# AetherMesh_Test_Fixture_Mezz_V1_0.net
KiCad netlist of a schematic drawn in EAGLE
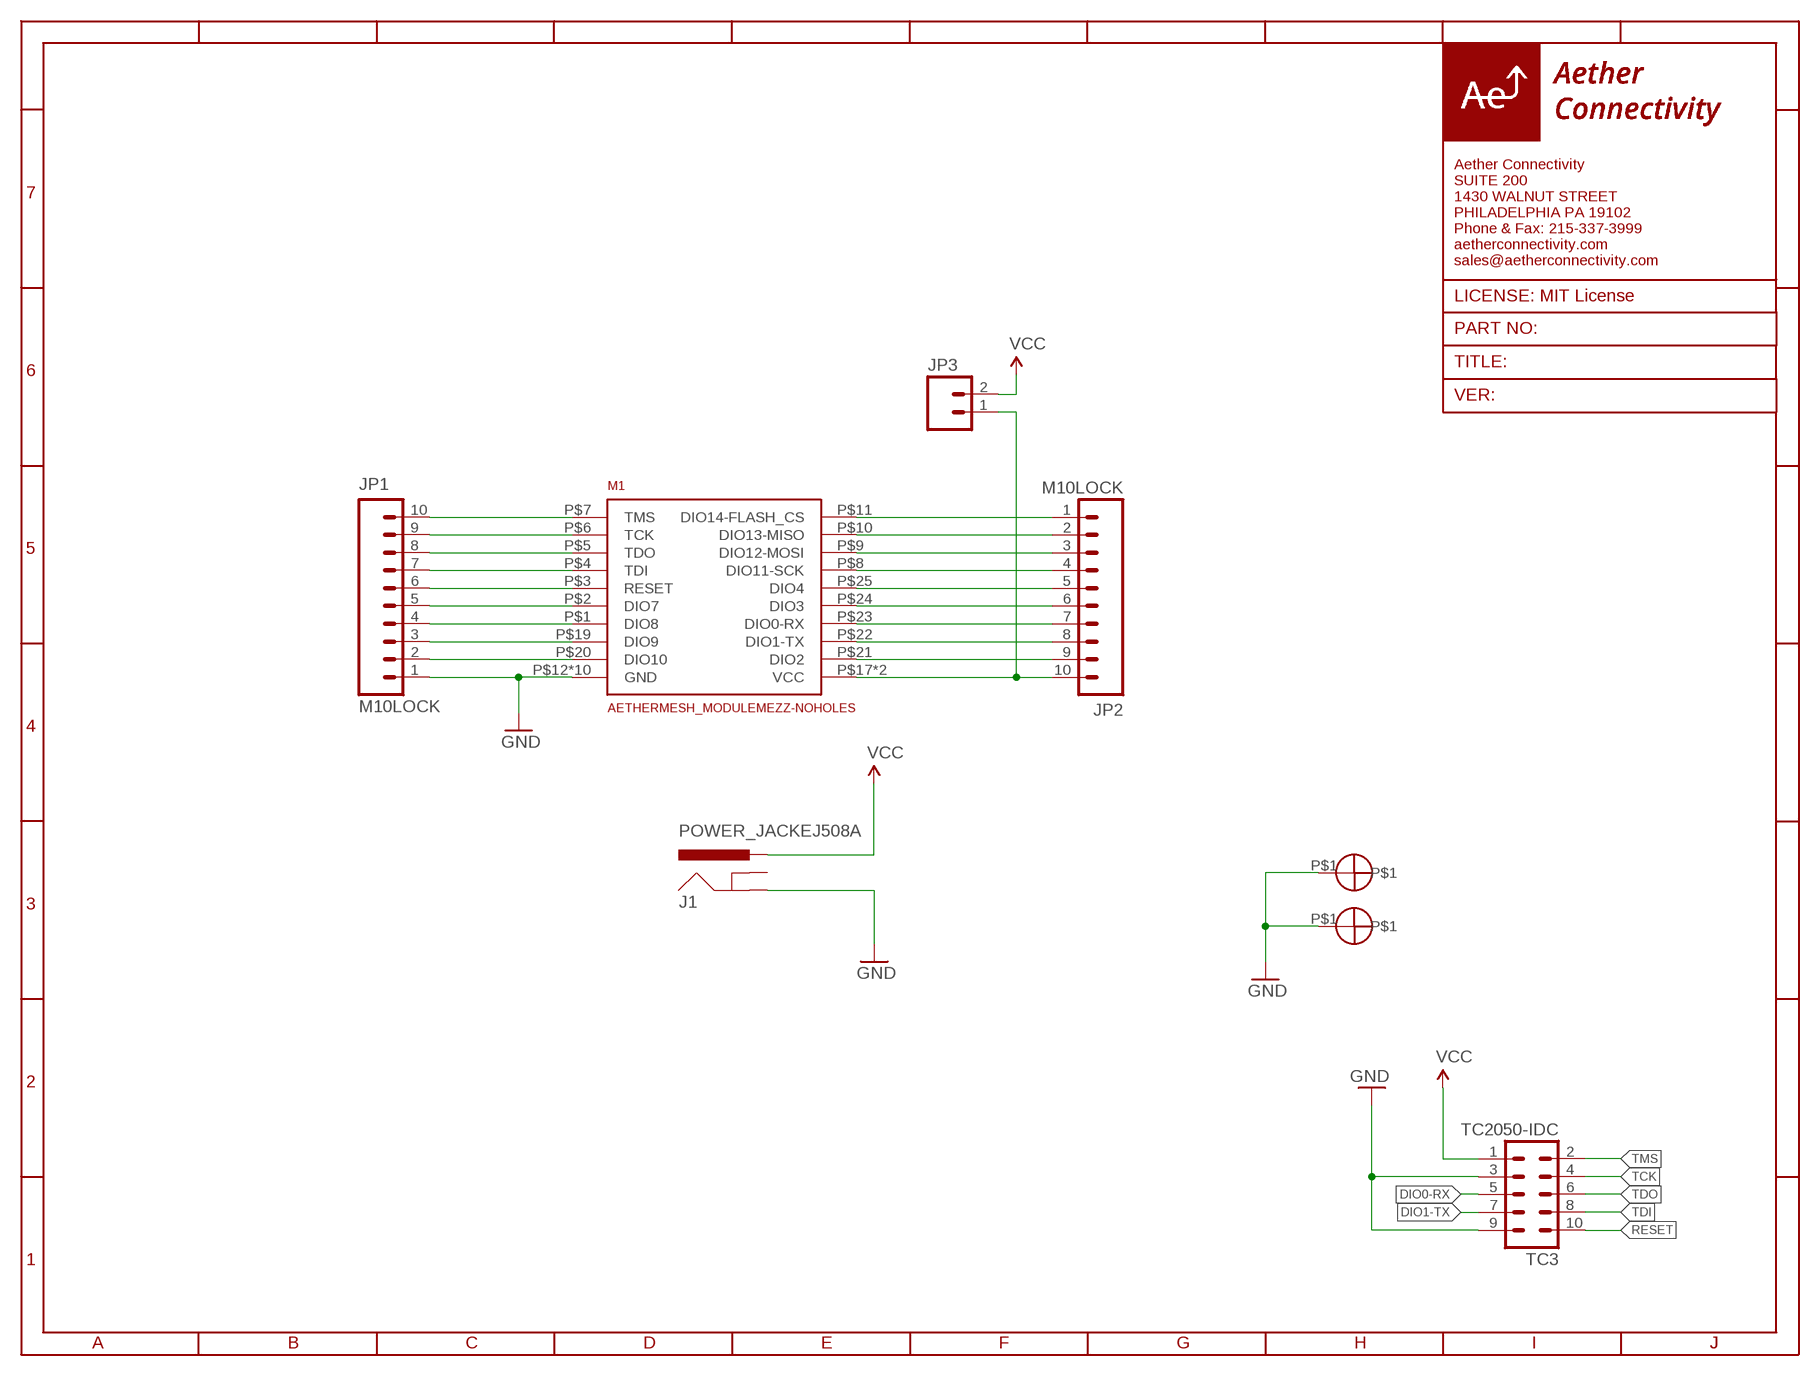
[diagram p0: schematic, sheet 1]

(export (version "E")
  (design (tool "Eeschema 10.0.6"))
  (components
    (comp (ref "J1")
      (value "POWER_JACKEJ508A")
      (footprint "eagle-import:DC_JACK_EJ508A")
      (libsource (lib "eagle-import") (part "POWER_JACKEJ508A"))
    )
    (comp (ref "JP1")
      (value "M10LOCK")
      (footprint "eagle-import:1X10_LOCK")
      (libsource (lib "eagle-import") (part "M10LOCK"))
    )
    (comp (ref "JP2")
      (value "M10LOCK")
      (footprint "eagle-import:1X10_LOCK")
      (libsource (lib "eagle-import") (part "M10LOCK"))
    )
    (comp (ref "JP3")
      (value "M02LOCK")
      (footprint "eagle-import:1X02_LOCK")
      (libsource (lib "eagle-import") (part "M02LOCK"))
    )
    (comp (ref "M1")
      (value "AETHERMESH_MODULEMEZZ-NOHOLES")
      (footprint "eagle-import:AETHERMESH_MEZZ_MOUNT_NOHOLES")
      (libsource (lib "eagle-import") (part "AETHERMESH_MODULEMEZZ-NOHOLES"))
    )
    (comp (ref "S1")
      (value "STANDOFFWURTH")
      (footprint "eagle-import:STANDOFF_WURTH_9774040243R")
      (libsource (lib "eagle-import") (part "STANDOFFWURTH"))
    )
    (comp (ref "S2")
      (value "STANDOFFWURTH")
      (footprint "eagle-import:STANDOFF_WURTH_9774040243R")
      (libsource (lib "eagle-import") (part "STANDOFFWURTH"))
    )
    (comp (ref "TC3")
      (value "TC2050-IDC")
      (footprint "eagle-import:TC2050-IDC")
      (libsource (lib "eagle-import") (part "TC2050-IDC"))
    )
  )
  (nets
    (net (code "1") (name "DIO0-RX") (class "Default")
      (node (ref "JP2") (pin "7") (pinfunction "7_7") (pintype "passive"))
      (node (ref "M1") (pin "P$23") (pinfunction "DIO0-RX_P$23") (pintype "bidirectional"))
      (node (ref "TC3") (pin "5") (pinfunction "5_5") (pintype "passive"))
    )
    (net (code "2") (name "DIO1-TX") (class "Default")
      (node (ref "JP2") (pin "8") (pinfunction "8_8") (pintype "passive"))
      (node (ref "M1") (pin "P$22") (pinfunction "DIO1-TX_P$22") (pintype "bidirectional"))
      (node (ref "TC3") (pin "7") (pinfunction "7_7") (pintype "passive"))
    )
    (net (code "3") (name "GND") (class "Default")
      (node (ref "J1") (pin "1") (pinfunction "GND_1") (pintype "bidirectional"))
      (node (ref "JP1") (pin "1") (pinfunction "1_1") (pintype "passive"))
      (node (ref "M1") (pin "P$12") (pinfunction "GND_P$12") (pintype "bidirectional"))
      (node (ref "M1") (pin "P$13") (pinfunction "GND_P$13") (pintype "bidirectional"))
      (node (ref "M1") (pin "P$14") (pinfunction "GND_P$14") (pintype "bidirectional"))
      (node (ref "M1") (pin "P$15") (pinfunction "GND_P$15") (pintype "bidirectional"))
      (node (ref "M1") (pin "P$16") (pinfunction "GND_P$16") (pintype "bidirectional"))
      (node (ref "M1") (pin "P$26") (pinfunction "GND_P$26") (pintype "bidirectional"))
      (node (ref "M1") (pin "P$27") (pinfunction "GND_P$27") (pintype "bidirectional"))
      (node (ref "M1") (pin "P$28") (pinfunction "GND_P$28") (pintype "bidirectional"))
      (node (ref "M1") (pin "P$29") (pinfunction "GND_P$29") (pintype "bidirectional"))
      (node (ref "M1") (pin "P$30") (pinfunction "GND_P$30") (pintype "bidirectional"))
      (node (ref "S1") (pin "P$1") (pinfunction "P$1_P$1") (pintype "bidirectional"))
      (node (ref "S2") (pin "P$1") (pinfunction "P$1_P$1") (pintype "bidirectional"))
      (node (ref "TC3") (pin "3") (pinfunction "3_3") (pintype "passive"))
      (node (ref "TC3") (pin "9") (pinfunction "9_9") (pintype "passive"))
    )
    (net (code "4") (name "Net-(JP2-Pad10)") (class "Default")
      (node (ref "JP2") (pin "10") (pinfunction "10_10") (pintype "passive"))
      (node (ref "JP3") (pin "1") (pinfunction "1_1") (pintype "passive"))
      (node (ref "M1") (pin "P$17") (pinfunction "VCC_P$17") (pintype "bidirectional"))
      (node (ref "M1") (pin "P$18") (pinfunction "VCC_P$18") (pintype "bidirectional"))
    )
    (net (code "5") (name "Net-(M1-DIO2)") (class "Default")
      (node (ref "JP2") (pin "9") (pinfunction "9_9") (pintype "passive"))
      (node (ref "M1") (pin "P$21") (pinfunction "DIO2_P$21") (pintype "bidirectional"))
    )
    (net (code "6") (name "Net-(M1-DIO3)") (class "Default")
      (node (ref "JP2") (pin "6") (pinfunction "6_6") (pintype "passive"))
      (node (ref "M1") (pin "P$24") (pinfunction "DIO3_P$24") (pintype "bidirectional"))
    )
    (net (code "7") (name "Net-(M1-DIO4)") (class "Default")
      (node (ref "JP2") (pin "5") (pinfunction "5_5") (pintype "passive"))
      (node (ref "M1") (pin "P$25") (pinfunction "DIO4_P$25") (pintype "bidirectional"))
    )
    (net (code "8") (name "Net-(M1-DIO7)") (class "Default")
      (node (ref "JP1") (pin "5") (pinfunction "5_5") (pintype "passive"))
      (node (ref "M1") (pin "P$2") (pinfunction "DIO7_P$2") (pintype "bidirectional"))
    )
    (net (code "9") (name "Net-(M1-DIO8)") (class "Default")
      (node (ref "JP1") (pin "4") (pinfunction "4_4") (pintype "passive"))
      (node (ref "M1") (pin "P$1") (pinfunction "DIO8_P$1") (pintype "bidirectional"))
    )
    (net (code "10") (name "Net-(M1-DIO9)") (class "Default")
      (node (ref "JP1") (pin "3") (pinfunction "3_3") (pintype "passive"))
      (node (ref "M1") (pin "P$19") (pinfunction "DIO9_P$19") (pintype "bidirectional"))
    )
    (net (code "11") (name "Net-(M1-DIO10)") (class "Default")
      (node (ref "JP1") (pin "2") (pinfunction "2_2") (pintype "passive"))
      (node (ref "M1") (pin "P$20") (pinfunction "DIO10_P$20") (pintype "bidirectional"))
    )
    (net (code "12") (name "Net-(M1-DIO11-SCK)") (class "Default")
      (node (ref "JP2") (pin "4") (pinfunction "4_4") (pintype "passive"))
      (node (ref "M1") (pin "P$8") (pinfunction "DIO11-SCK_P$8") (pintype "bidirectional"))
    )
    (net (code "13") (name "Net-(M1-DIO12-MOSI)") (class "Default")
      (node (ref "JP2") (pin "3") (pinfunction "3_3") (pintype "passive"))
      (node (ref "M1") (pin "P$9") (pinfunction "DIO12-MOSI_P$9") (pintype "bidirectional"))
    )
    (net (code "14") (name "Net-(M1-DIO13-MISO)") (class "Default")
      (node (ref "JP2") (pin "2") (pinfunction "2_2") (pintype "passive"))
      (node (ref "M1") (pin "P$10") (pinfunction "DIO13-MISO_P$10") (pintype "bidirectional"))
    )
    (net (code "15") (name "Net-(M1-DIO14-FLASH_CS)") (class "Default")
      (node (ref "JP2") (pin "1") (pinfunction "1_1") (pintype "passive"))
      (node (ref "M1") (pin "P$11") (pinfunction "DIO14-FLASH_CS_P$11") (pintype "bidirectional"))
    )
    (net (code "16") (name "RESET") (class "Default")
      (node (ref "JP1") (pin "6") (pinfunction "6_6") (pintype "passive"))
      (node (ref "M1") (pin "P$3") (pinfunction "RESET_P$3") (pintype "bidirectional"))
      (node (ref "TC3") (pin "10") (pinfunction "10_10") (pintype "passive"))
    )
    (net (code "17") (name "TCK") (class "Default")
      (node (ref "JP1") (pin "9") (pinfunction "9_9") (pintype "passive"))
      (node (ref "M1") (pin "P$6") (pinfunction "TCK_P$6") (pintype "bidirectional"))
      (node (ref "TC3") (pin "4") (pinfunction "4_4") (pintype "passive"))
    )
    (net (code "18") (name "TDI") (class "Default")
      (node (ref "JP1") (pin "7") (pinfunction "7_7") (pintype "passive"))
      (node (ref "M1") (pin "P$4") (pinfunction "TDI_P$4") (pintype "bidirectional"))
      (node (ref "TC3") (pin "8") (pinfunction "8_8") (pintype "passive"))
    )
    (net (code "19") (name "TDO") (class "Default")
      (node (ref "JP1") (pin "8") (pinfunction "8_8") (pintype "passive"))
      (node (ref "M1") (pin "P$5") (pinfunction "TDO_P$5") (pintype "bidirectional"))
      (node (ref "TC3") (pin "6") (pinfunction "6_6") (pintype "passive"))
    )
    (net (code "20") (name "TMS") (class "Default")
      (node (ref "JP1") (pin "10") (pinfunction "10_10") (pintype "passive"))
      (node (ref "M1") (pin "P$7") (pinfunction "TMS_P$7") (pintype "bidirectional"))
      (node (ref "TC3") (pin "2") (pinfunction "2_2") (pintype "passive"))
    )
    (net (code "21") (name "VCC") (class "Default")
      (node (ref "J1") (pin "3") (pinfunction "PWR_3") (pintype "bidirectional"))
      (node (ref "JP3") (pin "2") (pinfunction "2_2") (pintype "passive"))
      (node (ref "TC3") (pin "1") (pinfunction "1_1") (pintype "passive"))
    )
    (net (code "22") (name "unconnected-(J1-GNDBREAK-Pad2)") (class "Default")
      (node (ref "J1") (pin "2") (pinfunction "GNDBREAK_2") (pintype "bidirectional"))
    )
  )
)
